# 2_Safety_Relay.net
KiCad netlist of a schematic drawn in Altium Designer
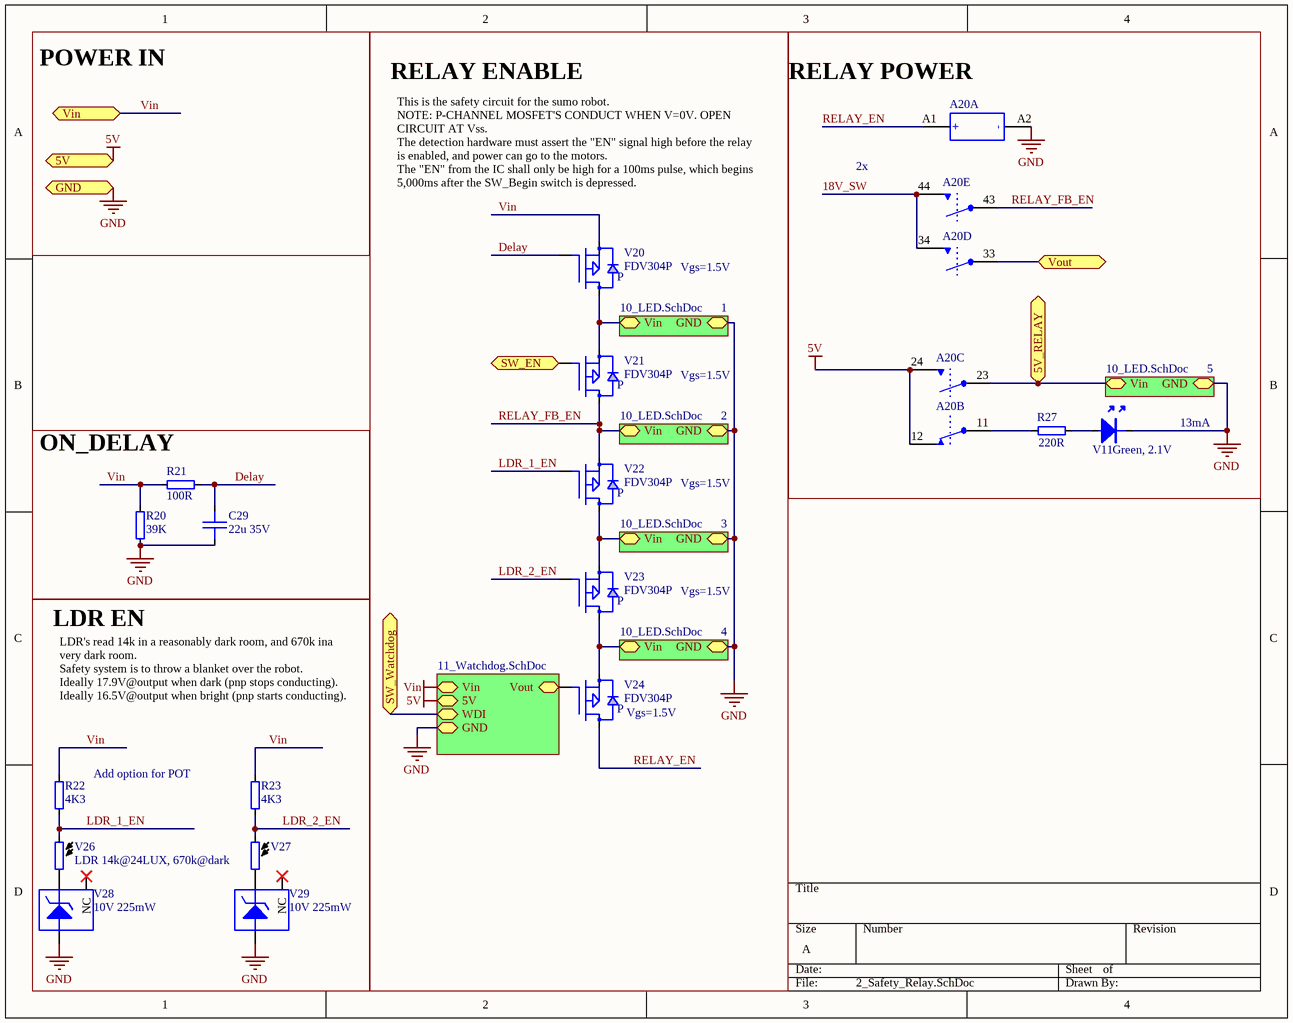
[diagram p0: 2_Safety_Relay.SchDoc]

(export (version "E")
  (design (tool "Eeschema 10.0.6"))
  (components
    (comp (ref "A20")
      (value "RELAY SAFETY 4PST 8A 18V")
      (footprint "RELAY-BRUMFIELD-4PST-3NO-1NC")
      (description "Safety Relay 4PST, 3NO 1 NC")
      (fields
        (field (name "MANUFACTURER") "TE Connectivity Potter & Brumfield Relays")
        (field (name "PARTNUMBER") "SR4M4018")
      )
      (libsource (lib "SVN_BOMGEN_Database_2014") (part "RELAY-4PST-3A1B"))
    )
    (comp (ref "C29")
      (value "22u 35V")
      (footprint "0805")
      (description "Capacitor")
      (fields
        (field (name "MANUFACTURER") "TDK")
        (field (name "PARTNUMBER") "C2012X5R1V226M125AC")
        (field (name "CHECKEDBY") "pfu")
      )
      (libsource (lib "SVN_BOMGEN_Database_2014") (part "CAP"))
    )
    (comp (ref "R20")
      (value "39K")
      (footprint "0805")
      (description "Resistor")
      (fields
        (field (name "MANUFACTURER") "Phycomp")
        (field (name "PARTNUMBER") "RC0805FR-0739KL")
        (field (name "CHECKEDBY") "ART")
      )
      (libsource (lib "SVN_BOMGEN_Database_2014") (part "RES"))
    )
    (comp (ref "R21")
      (value "100R")
      (footprint "0805")
      (description "Resistor")
      (fields
        (field (name "MANUFACTURER") "Phycomp")
        (field (name "PARTNUMBER") "RC0805FR-07100RL")
        (field (name "CHECKEDBY") "ART")
      )
      (libsource (lib "SVN_BOMGEN_Database_2014") (part "RES"))
    )
    (comp (ref "R22")
      (value "4K3")
      (footprint "0603")
      (description "Resistor")
      (fields
        (field (name "MANUFACTURER") "Phycomp")
        (field (name "PARTNUMBER") "RC0603FR-074K3L")
        (field (name "CHECKEDBY") "ART")
      )
      (libsource (lib "SVN_BOMGEN_Database_2014") (part "RES"))
    )
    (comp (ref "R23")
      (value "4K3")
      (footprint "0603")
      (description "Resistor")
      (fields
        (field (name "MANUFACTURER") "Phycomp")
        (field (name "PARTNUMBER") "RC0603FR-074K3L")
        (field (name "CHECKEDBY") "ART")
      )
      (libsource (lib "SVN_BOMGEN_Database_2014") (part "RES"))
    )
    (comp (ref "R27")
      (value "220R")
      (footprint "1206")
      (description "Resistor")
      (fields
        (field (name "MANUFACTURER") "Phycomp")
        (field (name "PARTNUMBER") "RC1206FR-07220RL")
        (field (name "CHECKEDBY") "ART")
      )
      (libsource (lib "SVN_BOMGEN_Database_2014") (part "RES"))
    )
    (comp (ref "V11")
      (value "Green, 2.1V")
      (footprint "LED-0805")
      (description "LED")
      (fields
        (field (name "MANUFACTURER") "Chicago Miniature Lighting")
        (field (name "PARTNUMBER") "CMD17-21UGC/TR8")
        (field (name "CHECKEDBY") "SAA")
      )
      (libsource (lib "SVN_BOMGEN_Database_2014") (part "LED"))
    )
    (comp (ref "V20")
      (value "FDV304P")
      (footprint "SOT23")
      (description "MOSFET P CHANNEL GENERIC SOT23")
      (fields (field (name "MANUFACTURER") "Fairchild") (field (name "CHECKEDBY") "AJR"))
      (libsource (lib "SVN_BOMGEN_Database_2014") (part "MOSFET-P-SOT23"))
    )
    (comp (ref "V21")
      (value "FDV304P")
      (footprint "SOT23")
      (description "MOSFET P CHANNEL GENERIC SOT23")
      (fields (field (name "MANUFACTURER") "Fairchild") (field (name "CHECKEDBY") "AJR"))
      (libsource (lib "SVN_BOMGEN_Database_2014") (part "MOSFET-P-SOT23"))
    )
    (comp (ref "V22")
      (value "FDV304P")
      (footprint "SOT23")
      (description "MOSFET P CHANNEL GENERIC SOT23")
      (fields (field (name "MANUFACTURER") "Fairchild") (field (name "CHECKEDBY") "AJR"))
      (libsource (lib "SVN_BOMGEN_Database_2014") (part "MOSFET-P-SOT23"))
    )
    (comp (ref "V23")
      (value "FDV304P")
      (footprint "SOT23")
      (description "MOSFET P CHANNEL GENERIC SOT23")
      (fields (field (name "MANUFACTURER") "Fairchild") (field (name "CHECKEDBY") "AJR"))
      (libsource (lib "SVN_BOMGEN_Database_2014") (part "MOSFET-P-SOT23"))
    )
    (comp (ref "V24")
      (value "FDV304P")
      (footprint "SOT23")
      (description "MOSFET P CHANNEL GENERIC SOT23")
      (fields (field (name "MANUFACTURER") "Fairchild") (field (name "CHECKEDBY") "AJR"))
      (libsource (lib "SVN_BOMGEN_Database_2014") (part "MOSFET-P-SOT23"))
    )
    (comp (ref "V26")
      (value "LDR 14k@24LUX, 670k@dark")
      (footprint "LDR_NSL-5112")
      (description "LDR")
      (fields (field (name "MANUFACTURER") "Luna Optoelectronics") (field (name "PARTNUMBER") "NSL-5112"))
      (libsource (lib "SVN_BOMGEN_Database_2014") (part "LDR"))
    )
    (comp (ref "V27")
      (value "LDR 14k@24LUX, 670k@dark")
      (footprint "LDR_NSL-5112")
      (description "LDR")
      (fields (field (name "MANUFACTURER") "Luna Optoelectronics") (field (name "PARTNUMBER") "NSL-5112"))
      (libsource (lib "SVN_BOMGEN_Database_2014") (part "LDR"))
    )
    (comp (ref "V28")
      (value "10V 225mW")
      (footprint "SOT23")
      (description "DIODE ZENER SOT23 a-z k-x nc-y")
      (fields (field (name "MANUFACTURER") "ON Semi") (field (name "PARTNUMBER") "BZX84C10LT1G"))
      (libsource (lib "SVN_BOMGEN_Database_2014") (part "ZENER-SOT23"))
    )
    (comp (ref "V29")
      (value "10V 225mW")
      (footprint "SOT23")
      (description "DIODE ZENER SOT23 a-z k-x nc-y")
      (fields (field (name "MANUFACTURER") "ON Semi") (field (name "PARTNUMBER") "BZX84C10LT1G"))
      (libsource (lib "SVN_BOMGEN_Database_2014") (part "ZENER-SOT23"))
    )
  )
  (nets
    (net (code "1") (name "/5V_RELAY") (class "Default")
      (node (ref "A20") (pin "23") (pinfunction "23_23") (pintype "passive"))
    )
    (net (code "2") (name "/18V_SW") (class "Default")
      (node (ref "A20") (pin "34") (pinfunction "34_34") (pintype "passive"))
      (node (ref "A20") (pin "44") (pinfunction "44_44") (pintype "passive"))
    )
    (net (code "3") (name "/Delay") (class "Default")
      (node (ref "C29") (pin "1") (pinfunction "1_1") (pintype "passive"))
      (node (ref "R21") (pin "2") (pinfunction "2_2") (pintype "passive"))
      (node (ref "V20") (pin "z") (pinfunction "gate_z") (pintype "passive"))
    )
    (net (code "4") (name "/LDR_1_EN") (class "Default")
      (node (ref "R22") (pin "1") (pinfunction "1_1") (pintype "passive"))
      (node (ref "V22") (pin "z") (pinfunction "gate_z") (pintype "passive"))
      (node (ref "V26") (pin "1") (pinfunction "1_1") (pintype "passive"))
    )
    (net (code "5") (name "/LDR_2_EN") (class "Default")
      (node (ref "R23") (pin "1") (pinfunction "1_1") (pintype "passive"))
      (node (ref "V23") (pin "z") (pinfunction "gate_z") (pintype "passive"))
      (node (ref "V27") (pin "1") (pinfunction "1_1") (pintype "passive"))
    )
    (net (code "6") (name "/RELAY_EN") (class "Default")
      (node (ref "A20") (pin "A1") (pinfunction "A1_A1") (pintype "passive"))
      (node (ref "V24") (pin "x") (pinfunction "d_x") (pintype "passive"))
    )
    (net (code "7") (name "/RELAY_FB_EN") (class "Default")
      (node (ref "A20") (pin "43") (pinfunction "43_43") (pintype "passive"))
      (node (ref "V21") (pin "x") (pinfunction "d_x") (pintype "passive"))
      (node (ref "V22") (pin "y") (pinfunction "s_y") (pintype "passive"))
    )
    (net (code "8") (name "/SW_EN") (class "Default")
      (node (ref "V21") (pin "z") (pinfunction "gate_z") (pintype "passive"))
    )
    (net (code "10") (name "/Vin_1") (class "Default")
      (node (ref "V22") (pin "x") (pinfunction "d_x") (pintype "passive"))
      (node (ref "V23") (pin "y") (pinfunction "s_y") (pintype "passive"))
    )
    (net (code "11") (name "/Vin_2") (class "Default")
      (node (ref "V23") (pin "x") (pinfunction "d_x") (pintype "passive"))
      (node (ref "V24") (pin "y") (pinfunction "s_y") (pintype "passive"))
    )
    (net (code "12") (name "/Vin_3") (class "Default")
      (node (ref "V20") (pin "x") (pinfunction "d_x") (pintype "passive"))
      (node (ref "V21") (pin "y") (pinfunction "s_y") (pintype "passive"))
    )
    (net (code "13") (name "/Vout") (class "Default")
      (node (ref "A20") (pin "33") (pinfunction "33_33") (pintype "passive"))
    )
    (net (code "14") (name "/Vout_1") (class "Default")
      (node (ref "V24") (pin "z") (pinfunction "gate_z") (pintype "passive"))
    )
    (net (code "15") (name "5V") (class "Default")
      (node (ref "A20") (pin "12") (pinfunction "12_12") (pintype "passive"))
      (node (ref "A20") (pin "24") (pinfunction "24_24") (pintype "passive"))
    )
    (net (code "16") (name "GND") (class "Default")
      (node (ref "A20") (pin "A2") (pinfunction "A2_A2") (pintype "passive"))
      (node (ref "C29") (pin "2") (pinfunction "2_2") (pintype "passive"))
      (node (ref "R20") (pin "1") (pinfunction "1_1") (pintype "passive"))
      (node (ref "V11") (pin "k") (pintype "passive"))
      (node (ref "V28") (pin "z") (pinfunction "a_z") (pintype "passive"))
      (node (ref "V29") (pin "z") (pinfunction "a_z") (pintype "passive"))
    )
    (net (code "17") (name "Net-(A20-Pad11)") (class "Default")
      (node (ref "A20") (pin "11") (pinfunction "11_11") (pintype "passive"))
      (node (ref "R27") (pin "1") (pinfunction "1_1") (pintype "passive"))
    )
    (net (code "18") (name "Net-(R27-Pad2)") (class "Default")
      (node (ref "R27") (pin "2") (pinfunction "2_2") (pintype "passive"))
      (node (ref "V11") (pin "a") (pintype "passive"))
    )
    (net (code "19") (name "Net-(V28-k)") (class "Default")
      (node (ref "V26") (pin "2") (pinfunction "2_2") (pintype "passive"))
      (node (ref "V28") (pin "x") (pinfunction "k_x") (pintype "passive"))
    )
    (net (code "20") (name "Net-(V29-k)") (class "Default")
      (node (ref "V27") (pin "2") (pinfunction "2_2") (pintype "passive"))
      (node (ref "V29") (pin "x") (pinfunction "k_x") (pintype "passive"))
    )
    (net (code "21") (name "Vin") (class "Default")
      (node (ref "R20") (pin "2") (pinfunction "2_2") (pintype "passive"))
      (node (ref "R21") (pin "1") (pinfunction "1_1") (pintype "passive"))
      (node (ref "R22") (pin "2") (pinfunction "2_2") (pintype "passive"))
      (node (ref "R23") (pin "2") (pinfunction "2_2") (pintype "passive"))
      (node (ref "V20") (pin "y") (pinfunction "s_y") (pintype "passive"))
    )
    (net (code "22") (name "unconnected-(V28-NC-Pady)") (class "Default")
      (node (ref "V28") (pin "y") (pinfunction "NC_y") (pintype "passive+no_connect"))
    )
    (net (code "23") (name "unconnected-(V29-NC-Pady)") (class "Default")
      (node (ref "V29") (pin "y") (pinfunction "NC_y") (pintype "passive+no_connect"))
    )
  )
)
